# PPG_Board.net
KiCad netlist of a schematic drawn in Altium Designer
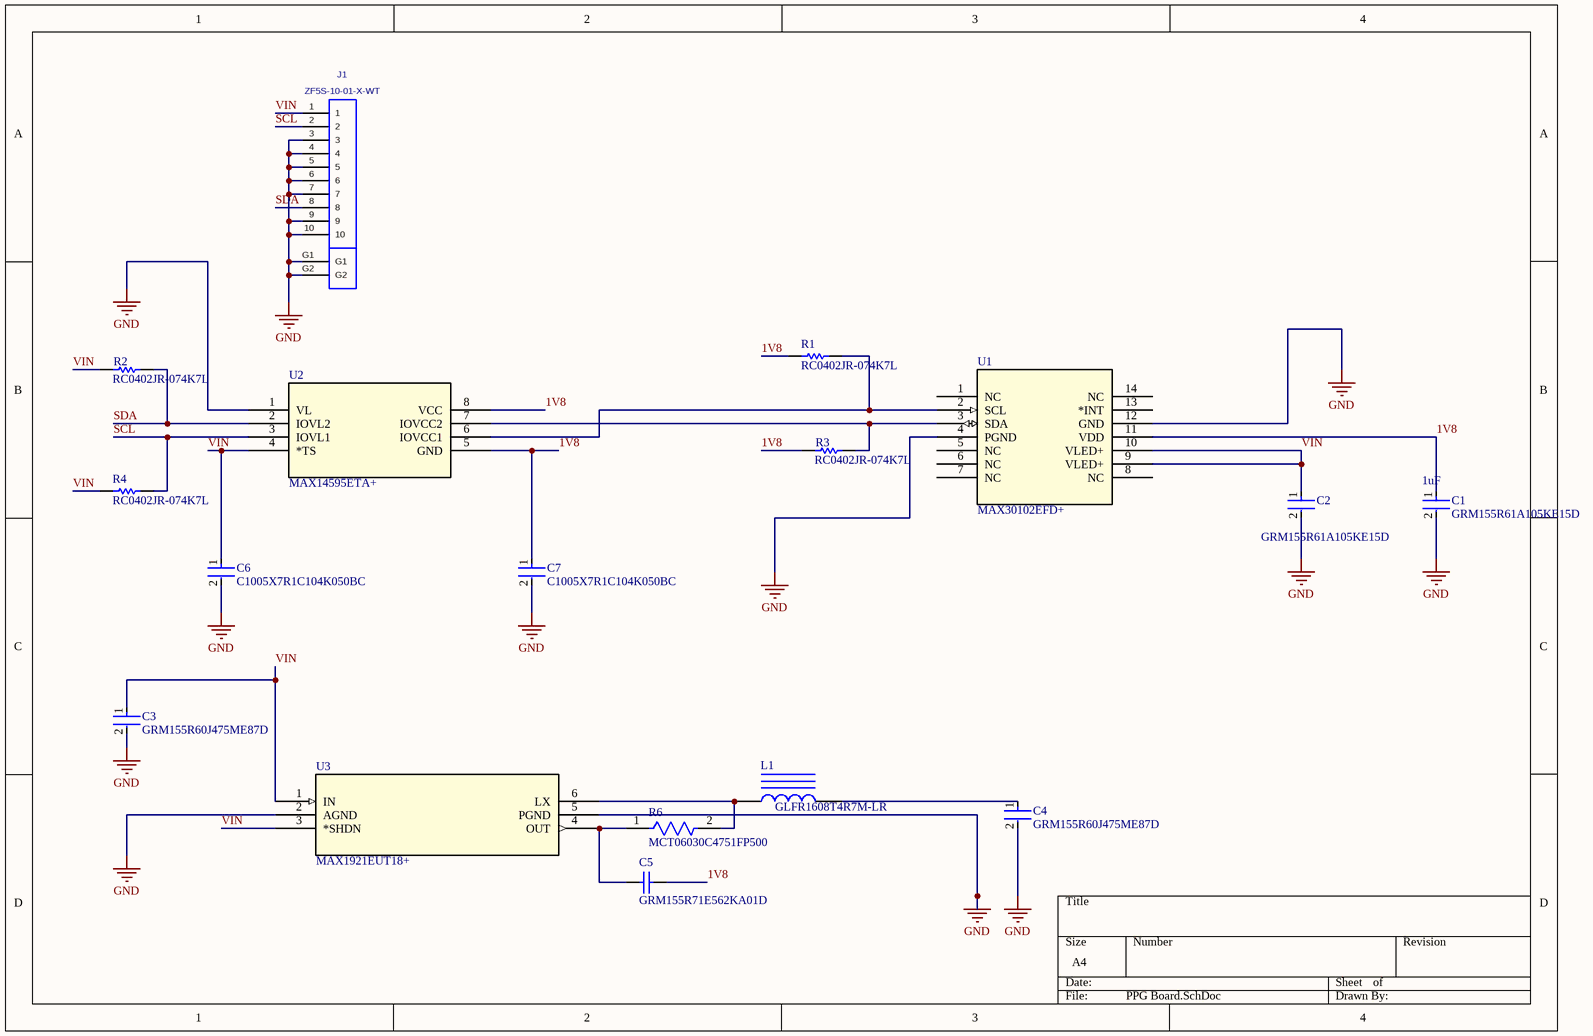
[diagram p0: PPG Board.SchDoc]

(export (version "E")
  (design (tool "Eeschema 10.0.6"))
  (components
    (comp (ref "C1")
      (value "GRM155R61A105KE15D")
      (footprint "FP-GRM15-0_1-MFG")
      (description "CAP CER 1UF 10V X5R 0402")
      (fields
        (field (name "OCTOPART") "https://octopart.com/grm155r61a105ke15d-murata-197442")
        (field (name "MANUFACTURER") "Murata")
        (field (name "ALTIUM_VALUE") "1uF")
      )
      (libsource (lib "Altium Content Vault") (part "02cd4be3c70576c341d710602a673aa"))
    )
    (comp (ref "C2")
      (value "GRM155R61A105KE15D")
      (footprint "FP-GRM15-0_1-MFG")
      (description "CAP CER 1UF 10V X5R 0402")
      (fields
        (field (name "OCTOPART") "https://octopart.com/grm155r61a105ke15d-murata-197442")
        (field (name "MANUFACTURER") "Murata")
      )
      (libsource (lib "Altium Content Vault") (part "02cd4be3c70576c341d710602a673aa"))
    )
    (comp (ref "C3")
      (value "GRM155R60J475ME87D")
      (footprint "FP-GRM155-0_15-MFG")
      (description "Chip Multilayer Ceramic Capacitors for General Purpose, 0402, 4.7uF, X5R, 15%, 20%, 6.3V")
      (fields (field (name "TOLERANCE") "20%") (field (name "VOLTAGE") "6.3V"))
      (libsource (lib "Altium Content Vault") (part "b4654b650e69147ec39a6b967a45e02"))
    )
    (comp (ref "C4")
      (value "GRM155R60J475ME87D")
      (footprint "FP-GRM155-0_15-MFG")
      (description "Chip Multilayer Ceramic Capacitors for General Purpose, 0402, 4.7uF, X5R, 15%, 20%, 6.3V")
      (fields (field (name "TOLERANCE") "20%") (field (name "VOLTAGE") "6.3V"))
      (libsource (lib "Altium Content Vault") (part "b4654b650e69147ec39a6b967a45e02"))
    )
    (comp (ref "C5")
      (value "GRM155R71E562KA01D")
      (footprint "CAPC1005X55X25ML05T10")
      (fields (field (name "MANUFACTURER") "Murata"))
      (libsource (lib "Altium Content Vault") (part "CAP"))
    )
    (comp (ref "C6")
      (value "C1005X7R1C104K050BC")
      (footprint "FP-C1005-050-0_05-MFG")
      (description "Multilayer Ceramic Capacitors 100nF ±10% 16V X7R SMD 0402")
      (fields (field (name "VOLTAGE") "16V") (field (name "TOLERANCE") "10%"))
      (libsource (lib "Altium Content Vault") (part "b4654b650e69147ec39a6b967a45e02"))
    )
    (comp (ref "C7")
      (value "C1005X7R1C104K050BC")
      (footprint "FP-C1005-050-0_05-MFG")
      (description "Multilayer Ceramic Capacitors 100nF ±10% 16V X7R SMD 0402")
      (fields (field (name "VOLTAGE") "16V") (field (name "TOLERANCE") "10%"))
      (libsource (lib "Altium Content Vault") (part "b4654b650e69147ec39a6b967a45e02"))
    )
    (comp (ref "J1")
      (value "ZF5S-10-01-X-WT")
      (footprint "ZF5S-10-01-X-WT")
      (description "ZERO INSERTION FORCE 0.5MM ASSEMBLY, 01 LEAD STYLE.")
      (fields (field (name "MANUFACTURER") "SAMTEC") (field (name "CREATED") "January 30, 2015 - Wendy Xin"))
      (libsource (lib "ZF5S-10-01-X-WT--Symbol-Altium-44987") (part "ZF5S-10-01-X-WT"))
    )
    (comp (ref "L1")
      (value "GLFR1608T4R7M-LR")
      (footprint "INDC1608X100X35LL20T15")
      (description "Chip Inductor, 4.7 uH, +/- 20%, -40 to 105 degC, 0603 (1608 Metric), RoHS, Tape and Reel")
      (fields (field (name "MANUFACTURER") "TDK") (field (name "TOLERANCE") "±20%"))
      (libsource (lib "Altium Content Vault") (part "IND-DOT-2_A"))
    )
    (comp (ref "R1")
      (value "RC0402JR-074K7L")
      (footprint "RESC1005X40X25LL05T10")
      (fields (field (name "MANUFACTURER") "Yageo / Phycomp"))
      (libsource (lib "Altium Content Vault") (part "RES"))
    )
    (comp (ref "R2")
      (value "RC0402JR-074K7L")
      (footprint "RESC1005X40X25LL05T10")
      (fields (field (name "MANUFACTURER") "Yageo / Phycomp"))
      (libsource (lib "Altium Content Vault") (part "RES"))
    )
    (comp (ref "R3")
      (value "RC0402JR-074K7L")
      (footprint "RESC1005X40X25LL05T10")
      (fields (field (name "MANUFACTURER") "Yageo / Phycomp"))
      (libsource (lib "Altium Content Vault") (part "RES"))
    )
    (comp (ref "R4")
      (value "RC0402JR-074K7L")
      (footprint "RESC1005X40X25LL05T10")
      (fields (field (name "MANUFACTURER") "Yageo / Phycomp"))
      (libsource (lib "Altium Content Vault") (part "RES"))
    )
    (comp (ref "R6")
      (value "MCT06030C4751FP500")
      (footprint "FP-MCT0603-IPC_A")
      (description "RES SMD 100 OHM 1% 1/8W 0603")
      (fields (field (name "TOLERANCE") "1%"))
      (libsource (lib "Altium Content Vault") (part "1029c3af85768c4190bb7ad29bc67b5"))
    )
    (comp (ref "U1")
      (value "MAX30102EFD+")
      (footprint "21-1048_F143A5+1_MXM")
      (description "No Description Available")
      (fields (field (name "COPYRIGHT") "Copyright (C) 2023 Ultra Librarian. All rights reserved."))
      (libsource (lib "MAX30102EFD&plus_") (part "MAX30102EFD+"))
    )
    (comp (ref "U2")
      (value "MAX14595ETA+")
      (footprint "21-0487_T822CN+1_MXM")
      (description "No Description Available")
      (fields (field (name "COPYRIGHT") "Copyright (C) 2023 Ultra Librarian. All rights reserved."))
      (libsource (lib "MAX14595ETA&plus_") (part "MAX14595ETA+"))
    )
    (comp (ref "U3")
      (value "MAX1921EUT18+")
      (footprint "21-0058I_MXM")
      (description "No Description Available")
      (fields (field (name "COPYRIGHT") "Copyright (C) 2023 Ultra Librarian. All rights reserved."))
      (libsource (lib "MAX1921EUT18&plus_") (part "MAX1921EUT18+"))
    )
  )
  (nets
    (net (code "1") (name "/1V8") (class "Default")
      (node (ref "C1") (pin "1") (pinfunction "1_1") (pintype "passive"))
      (node (ref "C5") (pin "2") (pinfunction "2_2") (pintype "passive"))
      (node (ref "C7") (pin "1") (pinfunction "1_1") (pintype "passive"))
      (node (ref "R1") (pin "1") (pinfunction "1_1") (pintype "passive"))
      (node (ref "R3") (pin "1") (pinfunction "1_1") (pintype "passive"))
      (node (ref "U1") (pin "11") (pinfunction "VDD_11") (pintype "power_in"))
      (node (ref "U2") (pin "5") (pinfunction "GND_5") (pintype "power_in"))
      (node (ref "U2") (pin "8") (pinfunction "VCC_8") (pintype "power_in"))
    )
    (net (code "2") (name "/SCL") (class "Default")
      (node (ref "J1") (pin "2") (pinfunction "2_2") (pintype "passive"))
      (node (ref "R4") (pin "2") (pinfunction "2_2") (pintype "passive"))
      (node (ref "U2") (pin "3") (pinfunction "IOVL1_3") (pintype "passive"))
    )
    (net (code "3") (name "/SDA") (class "Default")
      (node (ref "J1") (pin "8") (pinfunction "8_8") (pintype "passive"))
      (node (ref "R2") (pin "2") (pinfunction "2_2") (pintype "passive"))
      (node (ref "U2") (pin "2") (pinfunction "IOVL2_2") (pintype "passive"))
    )
    (net (code "4") (name "/VIN") (class "Default")
      (node (ref "C2") (pin "1") (pinfunction "1_1") (pintype "passive"))
      (node (ref "C3") (pin "1") (pinfunction "1_1") (pintype "passive"))
      (node (ref "C6") (pin "1") (pinfunction "1_1") (pintype "passive"))
      (node (ref "J1") (pin "1") (pinfunction "1_1") (pintype "passive"))
      (node (ref "R2") (pin "1") (pinfunction "1_1") (pintype "passive"))
      (node (ref "R4") (pin "1") (pinfunction "1_1") (pintype "passive"))
      (node (ref "U1") (pin "10") (pinfunction "VLED+_10") (pintype "passive"))
      (node (ref "U1") (pin "9") (pinfunction "VLED+_9") (pintype "passive"))
      (node (ref "U2") (pin "4") (pinfunction "*TS_4") (pintype "passive"))
      (node (ref "U3") (pin "1") (pinfunction "IN_1") (pintype "input"))
      (node (ref "U3") (pin "3") (pinfunction "*SHDN_3") (pintype "passive"))
    )
    (net (code "5") (name "GND") (class "Default")
      (node (ref "C1") (pin "2") (pinfunction "2_2") (pintype "passive"))
      (node (ref "C2") (pin "2") (pinfunction "2_2") (pintype "passive"))
      (node (ref "C3") (pin "2") (pinfunction "2_2") (pintype "passive"))
      (node (ref "C4") (pin "2") (pinfunction "2_2") (pintype "passive"))
      (node (ref "C6") (pin "2") (pinfunction "2_2") (pintype "passive"))
      (node (ref "C7") (pin "2") (pinfunction "2_2") (pintype "passive"))
      (node (ref "J1") (pin "10") (pinfunction "10_10") (pintype "passive"))
      (node (ref "J1") (pin "3") (pinfunction "3_3") (pintype "passive"))
      (node (ref "J1") (pin "4") (pinfunction "4_4") (pintype "passive"))
      (node (ref "J1") (pin "5") (pinfunction "5_5") (pintype "passive"))
      (node (ref "J1") (pin "6") (pinfunction "6_6") (pintype "passive"))
      (node (ref "J1") (pin "7") (pinfunction "7_7") (pintype "passive"))
      (node (ref "J1") (pin "9") (pinfunction "9_9") (pintype "passive"))
      (node (ref "J1") (pin "G1") (pinfunction "G1_G1") (pintype "passive"))
      (node (ref "J1") (pin "G2") (pinfunction "G2_G2") (pintype "passive"))
      (node (ref "U1") (pin "12") (pinfunction "GND_12") (pintype "power_in"))
      (node (ref "U1") (pin "4") (pinfunction "PGND_4") (pintype "power_in"))
      (node (ref "U2") (pin "1") (pinfunction "VL_1") (pintype "power_in"))
      (node (ref "U3") (pin "2") (pinfunction "AGND_2") (pintype "power_in"))
      (node (ref "U3") (pin "5") (pinfunction "PGND_5") (pintype "power_in"))
    )
    (net (code "6") (name "Net-(C4-Pad1)") (class "Default")
      (node (ref "C4") (pin "1") (pinfunction "1_1") (pintype "passive"))
      (node (ref "L1") (pin "2") (pinfunction "2_2") (pintype "passive"))
    )
    (net (code "7") (name "Net-(U1-SCL)") (class "Default")
      (node (ref "R1") (pin "2") (pinfunction "2_2") (pintype "passive"))
      (node (ref "U1") (pin "2") (pinfunction "SCL_2") (pintype "input"))
      (node (ref "U2") (pin "6") (pinfunction "IOVCC1_6") (pintype "passive"))
    )
    (net (code "8") (name "Net-(U1-SDA)") (class "Default")
      (node (ref "R3") (pin "2") (pinfunction "2_2") (pintype "passive"))
      (node (ref "U1") (pin "3") (pinfunction "SDA_3") (pintype "bidirectional"))
      (node (ref "U2") (pin "7") (pinfunction "IOVCC2_7") (pintype "passive"))
    )
    (net (code "9") (name "Net-(U3-LX)") (class "Default")
      (node (ref "L1") (pin "1") (pinfunction "1_1") (pintype "passive"))
      (node (ref "R6") (pin "2") (pinfunction "2_2") (pintype "passive"))
      (node (ref "U3") (pin "6") (pinfunction "LX_6") (pintype "passive"))
    )
    (net (code "10") (name "Net-(U3-OUT)") (class "Default")
      (node (ref "C5") (pin "1") (pinfunction "1_1") (pintype "passive"))
      (node (ref "R6") (pin "1") (pinfunction "1_1") (pintype "passive"))
      (node (ref "U3") (pin "4") (pinfunction "OUT_4") (pintype "output"))
    )
    (net (code "11") (name "unconnected-(U1-*INT-Pad13)") (class "Default")
      (node (ref "U1") (pin "13") (pinfunction "*INT_13") (pintype "passive"))
    )
    (net (code "12") (name "unconnected-(U1-NC-Pad1)") (class "Default")
      (node (ref "U1") (pin "1") (pinfunction "NC_1") (pintype "passive"))
    )
    (net (code "13") (name "unconnected-(U1-NC-Pad5)") (class "Default")
      (node (ref "U1") (pin "5") (pinfunction "NC_5") (pintype "passive"))
    )
    (net (code "14") (name "unconnected-(U1-NC-Pad6)") (class "Default")
      (node (ref "U1") (pin "6") (pinfunction "NC_6") (pintype "passive"))
    )
    (net (code "15") (name "unconnected-(U1-NC-Pad7)") (class "Default")
      (node (ref "U1") (pin "7") (pinfunction "NC_7") (pintype "passive"))
    )
    (net (code "16") (name "unconnected-(U1-NC-Pad8)") (class "Default")
      (node (ref "U1") (pin "8") (pinfunction "NC_8") (pintype "passive"))
    )
    (net (code "17") (name "unconnected-(U1-NC-Pad14)") (class "Default")
      (node (ref "U1") (pin "14") (pinfunction "NC_14") (pintype "passive"))
    )
  )
)
